# mitosis.net
KiCad netlist of a schematic drawn in Altium Designer
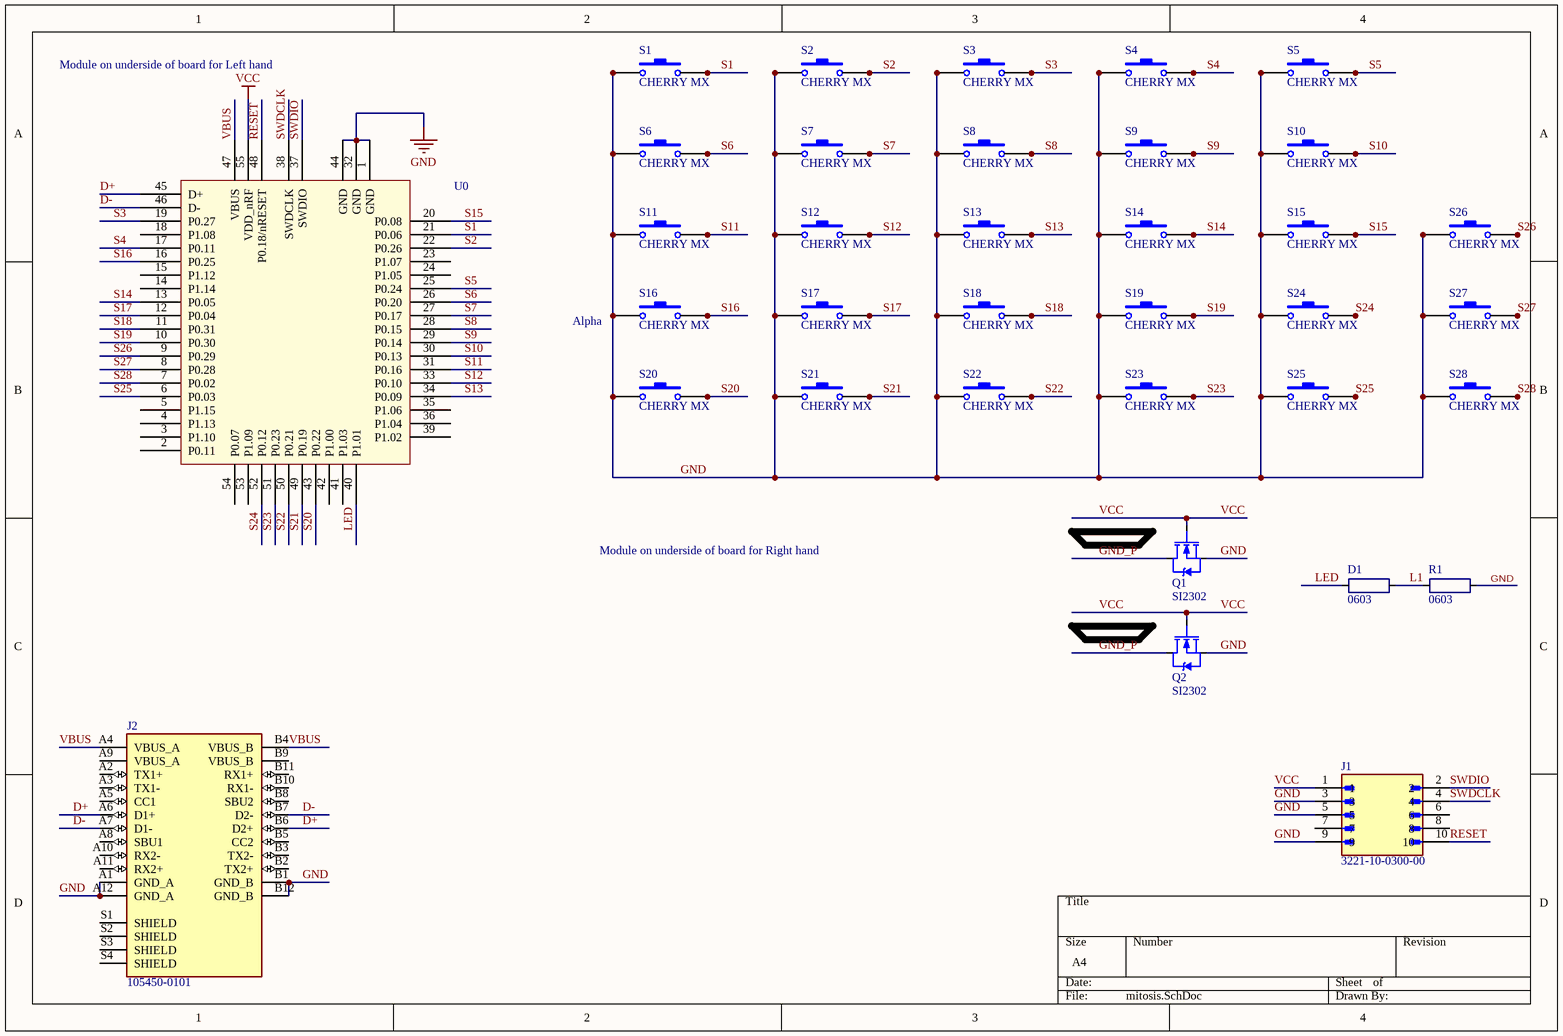
[diagram p0: mitosis.SchDoc]

(export (version "E")
  (design (tool "Eeschema 10.0.6"))
  (components
    (comp (ref "D1") (value "0603") (footprint "RESC2012X06N") (libsource (lib "SK") (part "0603")))
    (comp (ref "J1")
      (value "3221-10-0300-00")
      (footprint "mitosis:CNC_3221-10-0300-00")
      (description "Conn Shrouded Header HDR 10 POS 1.27mm Solder ST SMD T/R")
      (fields (field (name "MF") "CNC Tech") (field (name "MANUFACTURER PART NUMBER") "3221-10-0300-00-TR"))
      (libsource (lib "mitosis") (part "3221-10-0300-00"))
    )
    (comp (ref "J2")
      (value "105450-0101")
      (footprint "mitosis:MOLEX_105450-0101")
      (description "Conn USB 3.1 Type C F 24 POS Solder RA SMD 24 Terminal 1 Port USB 3.1 T/R")
      (fields (field (name "MANUFACTURER") "Molex"))
      (libsource (lib "mitosis") (part "105450-0101"))
    )
    (comp (ref "Q1")
      (value "SI2302")
      (footprint "SOT-23")
      (description "N-Channel Logic MOSFET")
      (fields (field (name "PUBLISHER") "Altium Limited"))
      (libsource (lib "SK") (part "SI2302"))
    )
    (comp (ref "Q2")
      (value "SI2302")
      (footprint "SOT-23")
      (description "N-Channel Logic MOSFET")
      (fields (field (name "PUBLISHER") "Altium Limited"))
      (libsource (lib "SK") (part "SI2302"))
    )
    (comp (ref "R1") (value "0603") (footprint "RESC2012X06N") (libsource (lib "SK") (part "0603")))
    (comp (ref "S1")
      (value "CHERRY MX")
      (footprint "cherry")
      (description "Switch")
      (fields (field (name "PUBLISHER") "Altium Limited"))
      (libsource (lib "SK") (part "CHERRY MX"))
    )
    (comp (ref "S2")
      (value "CHERRY MX")
      (footprint "cherry")
      (description "Switch")
      (fields (field (name "PUBLISHER") "Altium Limited"))
      (libsource (lib "SK") (part "CHERRY MX"))
    )
    (comp (ref "S3")
      (value "CHERRY MX")
      (footprint "cherry")
      (description "Switch")
      (fields (field (name "PUBLISHER") "Altium Limited"))
      (libsource (lib "SK") (part "CHERRY MX"))
    )
    (comp (ref "S4")
      (value "CHERRY MX")
      (footprint "cherry")
      (description "Switch")
      (fields (field (name "PUBLISHER") "Altium Limited"))
      (libsource (lib "SK") (part "CHERRY MX"))
    )
    (comp (ref "S5")
      (value "CHERRY MX")
      (footprint "cherry")
      (description "Switch")
      (fields (field (name "PUBLISHER") "Altium Limited"))
      (libsource (lib "SK") (part "CHERRY MX"))
    )
    (comp (ref "S6")
      (value "CHERRY MX")
      (footprint "cherry")
      (description "Switch")
      (fields (field (name "PUBLISHER") "Altium Limited"))
      (libsource (lib "SK") (part "CHERRY MX"))
    )
    (comp (ref "S7")
      (value "CHERRY MX")
      (footprint "cherry")
      (description "Switch")
      (fields (field (name "PUBLISHER") "Altium Limited"))
      (libsource (lib "SK") (part "CHERRY MX"))
    )
    (comp (ref "S8")
      (value "CHERRY MX")
      (footprint "cherry")
      (description "Switch")
      (fields (field (name "PUBLISHER") "Altium Limited"))
      (libsource (lib "SK") (part "CHERRY MX"))
    )
    (comp (ref "S9")
      (value "CHERRY MX")
      (footprint "cherry")
      (description "Switch")
      (fields (field (name "PUBLISHER") "Altium Limited"))
      (libsource (lib "SK") (part "CHERRY MX"))
    )
    (comp (ref "S10")
      (value "CHERRY MX")
      (footprint "cherry")
      (description "Switch")
      (fields (field (name "PUBLISHER") "Altium Limited"))
      (libsource (lib "SK") (part "CHERRY MX"))
    )
    (comp (ref "S11")
      (value "CHERRY MX")
      (footprint "cherry")
      (description "Switch")
      (fields (field (name "PUBLISHER") "Altium Limited"))
      (libsource (lib "SK") (part "CHERRY MX"))
    )
    (comp (ref "S12")
      (value "CHERRY MX")
      (footprint "cherry")
      (description "Switch")
      (fields (field (name "PUBLISHER") "Altium Limited"))
      (libsource (lib "SK") (part "CHERRY MX"))
    )
    (comp (ref "S13")
      (value "CHERRY MX")
      (footprint "cherry")
      (description "Switch")
      (fields (field (name "PUBLISHER") "Altium Limited"))
      (libsource (lib "SK") (part "CHERRY MX"))
    )
    (comp (ref "S14")
      (value "CHERRY MX")
      (footprint "cherry")
      (description "Switch")
      (fields (field (name "PUBLISHER") "Altium Limited"))
      (libsource (lib "SK") (part "CHERRY MX"))
    )
    (comp (ref "S15")
      (value "CHERRY MX")
      (footprint "cherry")
      (description "Switch")
      (fields (field (name "PUBLISHER") "Altium Limited"))
      (libsource (lib "SK") (part "CHERRY MX"))
    )
    (comp (ref "S16")
      (value "CHERRY MX")
      (footprint "cherry")
      (description "Switch")
      (fields (field (name "PUBLISHER") "Altium Limited"))
      (libsource (lib "SK") (part "CHERRY MX"))
    )
    (comp (ref "S17")
      (value "CHERRY MX")
      (footprint "cherry")
      (description "Switch")
      (fields (field (name "PUBLISHER") "Altium Limited"))
      (libsource (lib "SK") (part "CHERRY MX"))
    )
    (comp (ref "S18")
      (value "CHERRY MX")
      (footprint "cherry")
      (description "Switch")
      (fields (field (name "PUBLISHER") "Altium Limited"))
      (libsource (lib "SK") (part "CHERRY MX"))
    )
    (comp (ref "S19")
      (value "CHERRY MX")
      (footprint "cherry")
      (description "Switch")
      (fields (field (name "PUBLISHER") "Altium Limited"))
      (libsource (lib "SK") (part "CHERRY MX"))
    )
    (comp (ref "S20")
      (value "CHERRY MX")
      (footprint "cherry")
      (description "Switch")
      (fields (field (name "PUBLISHER") "Altium Limited"))
      (libsource (lib "SK") (part "CHERRY MX"))
    )
    (comp (ref "S21")
      (value "CHERRY MX")
      (footprint "cherry")
      (description "Switch")
      (fields (field (name "PUBLISHER") "Altium Limited"))
      (libsource (lib "SK") (part "CHERRY MX"))
    )
    (comp (ref "S22")
      (value "CHERRY MX")
      (footprint "cherry")
      (description "Switch")
      (fields (field (name "PUBLISHER") "Altium Limited"))
      (libsource (lib "SK") (part "CHERRY MX"))
    )
    (comp (ref "S23")
      (value "CHERRY MX")
      (footprint "cherry")
      (description "Switch")
      (fields (field (name "PUBLISHER") "Altium Limited"))
      (libsource (lib "SK") (part "CHERRY MX"))
    )
    (comp (ref "S24")
      (value "CHERRY MX")
      (footprint "cherry")
      (description "Switch")
      (fields (field (name "PUBLISHER") "Altium Limited"))
      (libsource (lib "mitosis") (part "CHERRY MX"))
    )
    (comp (ref "S25")
      (value "CHERRY MX")
      (footprint "cherry")
      (description "Switch")
      (fields (field (name "PUBLISHER") "Altium Limited"))
      (libsource (lib "mitosis") (part "CHERRY MX"))
    )
    (comp (ref "S26")
      (value "CHERRY MX")
      (footprint "cherry")
      (description "Switch")
      (fields (field (name "PUBLISHER") "Altium Limited"))
      (libsource (lib "mitosis") (part "CHERRY MX"))
    )
    (comp (ref "S27")
      (value "CHERRY MX")
      (footprint "cherry")
      (description "Switch")
      (fields (field (name "PUBLISHER") "Altium Limited"))
      (libsource (lib "mitosis") (part "CHERRY MX"))
    )
    (comp (ref "S28")
      (value "CHERRY MX")
      (footprint "cherry")
      (description "Switch")
      (fields (field (name "PUBLISHER") "Altium Limited"))
      (libsource (lib "mitosis") (part "CHERRY MX"))
    )
    (comp (ref "U0")
      (value "Core52840 (B)")
      (footprint "Core52840")
      (description "NRF52840 (B)")
      (libsource (lib "mitosis") (part "Core52840 (B)"))
    )
  )
  (nets
    (net (code "1") (name "/D+") (class "Default")
      (node (ref "J2") (pin "A6") (pinfunction "D1+_A6") (pintype "bidirectional"))
      (node (ref "J2") (pin "B6") (pinfunction "D2+_B6") (pintype "bidirectional"))
      (node (ref "U0") (pin "45") (pinfunction "D+_45") (pintype "passive"))
    )
    (net (code "2") (name "/D-") (class "Default")
      (node (ref "J2") (pin "A7") (pinfunction "D1-_A7") (pintype "bidirectional"))
      (node (ref "J2") (pin "B7") (pinfunction "D2-_B7") (pintype "bidirectional"))
      (node (ref "U0") (pin "46") (pinfunction "D-_46") (pintype "passive"))
    )
    (net (code "3") (name "/GND_P") (class "Default")
      (node (ref "Q1") (pin "3") (pinfunction "D_3") (pintype "passive"))
      (node (ref "Q2") (pin "3") (pinfunction "D_3") (pintype "passive"))
    )
    (net (code "4") (name "/L1") (class "Default")
      (node (ref "D1") (pin "1") (pinfunction "1_1") (pintype "passive"))
      (node (ref "R1") (pin "2") (pinfunction "2_2") (pintype "passive"))
    )
    (net (code "5") (name "/LED") (class "Default")
      (node (ref "D1") (pin "2") (pinfunction "2_2") (pintype "passive"))
      (node (ref "U0") (pin "40") (pinfunction "P1.01_40") (pintype "passive"))
    )
    (net (code "6") (name "/RESET") (class "Default")
      (node (ref "J1") (pin "10") (pinfunction "10_10") (pintype "passive"))
      (node (ref "U0") (pin "48") (pinfunction "P0.18/nRESET_48") (pintype "passive"))
    )
    (net (code "7") (name "/S1") (class "Default")
      (node (ref "S1") (pin "10") (pinfunction "10_10") (pintype "passive"))
      (node (ref "S1") (pin "12") (pinfunction "12_12") (pintype "passive"))
      (node (ref "S1") (pin "2") (pinfunction "2_2") (pintype "passive"))
      (node (ref "S1") (pin "4") (pinfunction "4_4") (pintype "passive"))
      (node (ref "S1") (pin "6") (pinfunction "6_6") (pintype "passive"))
      (node (ref "S1") (pin "8") (pinfunction "8_8") (pintype "passive"))
      (node (ref "U0") (pin "21") (pinfunction "P0.06_21") (pintype "passive"))
    )
    (net (code "8") (name "/S2") (class "Default")
      (node (ref "S2") (pin "10") (pinfunction "10_10") (pintype "passive"))
      (node (ref "S2") (pin "12") (pinfunction "12_12") (pintype "passive"))
      (node (ref "S2") (pin "2") (pinfunction "2_2") (pintype "passive"))
      (node (ref "S2") (pin "4") (pinfunction "4_4") (pintype "passive"))
      (node (ref "S2") (pin "6") (pinfunction "6_6") (pintype "passive"))
      (node (ref "S2") (pin "8") (pinfunction "8_8") (pintype "passive"))
      (node (ref "U0") (pin "22") (pinfunction "P0.26_22") (pintype "passive"))
    )
    (net (code "9") (name "/S3") (class "Default")
      (node (ref "S3") (pin "10") (pinfunction "10_10") (pintype "passive"))
      (node (ref "S3") (pin "12") (pinfunction "12_12") (pintype "passive"))
      (node (ref "S3") (pin "2") (pinfunction "2_2") (pintype "passive"))
      (node (ref "S3") (pin "4") (pinfunction "4_4") (pintype "passive"))
      (node (ref "S3") (pin "6") (pinfunction "6_6") (pintype "passive"))
      (node (ref "S3") (pin "8") (pinfunction "8_8") (pintype "passive"))
      (node (ref "U0") (pin "19") (pinfunction "P0.27_19") (pintype "passive"))
    )
    (net (code "10") (name "/S4") (class "Default")
      (node (ref "S4") (pin "10") (pinfunction "10_10") (pintype "passive"))
      (node (ref "S4") (pin "12") (pinfunction "12_12") (pintype "passive"))
      (node (ref "S4") (pin "2") (pinfunction "2_2") (pintype "passive"))
      (node (ref "S4") (pin "4") (pinfunction "4_4") (pintype "passive"))
      (node (ref "S4") (pin "6") (pinfunction "6_6") (pintype "passive"))
      (node (ref "S4") (pin "8") (pinfunction "8_8") (pintype "passive"))
      (node (ref "U0") (pin "17") (pinfunction "P0.11_17") (pintype "passive"))
    )
    (net (code "11") (name "/S5") (class "Default")
      (node (ref "S5") (pin "10") (pinfunction "10_10") (pintype "passive"))
      (node (ref "S5") (pin "12") (pinfunction "12_12") (pintype "passive"))
      (node (ref "S5") (pin "2") (pinfunction "2_2") (pintype "passive"))
      (node (ref "S5") (pin "4") (pinfunction "4_4") (pintype "passive"))
      (node (ref "S5") (pin "6") (pinfunction "6_6") (pintype "passive"))
      (node (ref "S5") (pin "8") (pinfunction "8_8") (pintype "passive"))
      (node (ref "U0") (pin "25") (pinfunction "P0.24_25") (pintype "passive"))
    )
    (net (code "12") (name "/S6") (class "Default")
      (node (ref "S6") (pin "10") (pinfunction "10_10") (pintype "passive"))
      (node (ref "S6") (pin "12") (pinfunction "12_12") (pintype "passive"))
      (node (ref "S6") (pin "2") (pinfunction "2_2") (pintype "passive"))
      (node (ref "S6") (pin "4") (pinfunction "4_4") (pintype "passive"))
      (node (ref "S6") (pin "6") (pinfunction "6_6") (pintype "passive"))
      (node (ref "S6") (pin "8") (pinfunction "8_8") (pintype "passive"))
      (node (ref "U0") (pin "26") (pinfunction "P0.20_26") (pintype "passive"))
    )
    (net (code "13") (name "/S7") (class "Default")
      (node (ref "S7") (pin "10") (pinfunction "10_10") (pintype "passive"))
      (node (ref "S7") (pin "12") (pinfunction "12_12") (pintype "passive"))
      (node (ref "S7") (pin "2") (pinfunction "2_2") (pintype "passive"))
      (node (ref "S7") (pin "4") (pinfunction "4_4") (pintype "passive"))
      (node (ref "S7") (pin "6") (pinfunction "6_6") (pintype "passive"))
      (node (ref "S7") (pin "8") (pinfunction "8_8") (pintype "passive"))
      (node (ref "U0") (pin "27") (pinfunction "P0.17_27") (pintype "passive"))
    )
    (net (code "14") (name "/S8") (class "Default")
      (node (ref "S8") (pin "10") (pinfunction "10_10") (pintype "passive"))
      (node (ref "S8") (pin "12") (pinfunction "12_12") (pintype "passive"))
      (node (ref "S8") (pin "2") (pinfunction "2_2") (pintype "passive"))
      (node (ref "S8") (pin "4") (pinfunction "4_4") (pintype "passive"))
      (node (ref "S8") (pin "6") (pinfunction "6_6") (pintype "passive"))
      (node (ref "S8") (pin "8") (pinfunction "8_8") (pintype "passive"))
      (node (ref "U0") (pin "28") (pinfunction "P0.15_28") (pintype "passive"))
    )
    (net (code "15") (name "/S9") (class "Default")
      (node (ref "S9") (pin "10") (pinfunction "10_10") (pintype "passive"))
      (node (ref "S9") (pin "12") (pinfunction "12_12") (pintype "passive"))
      (node (ref "S9") (pin "2") (pinfunction "2_2") (pintype "passive"))
      (node (ref "S9") (pin "4") (pinfunction "4_4") (pintype "passive"))
      (node (ref "S9") (pin "6") (pinfunction "6_6") (pintype "passive"))
      (node (ref "S9") (pin "8") (pinfunction "8_8") (pintype "passive"))
      (node (ref "U0") (pin "29") (pinfunction "P0.14_29") (pintype "passive"))
    )
    (net (code "16") (name "/S10") (class "Default")
      (node (ref "S10") (pin "10") (pinfunction "10_10") (pintype "passive"))
      (node (ref "S10") (pin "12") (pinfunction "12_12") (pintype "passive"))
      (node (ref "S10") (pin "2") (pinfunction "2_2") (pintype "passive"))
      (node (ref "S10") (pin "4") (pinfunction "4_4") (pintype "passive"))
      (node (ref "S10") (pin "6") (pinfunction "6_6") (pintype "passive"))
      (node (ref "S10") (pin "8") (pinfunction "8_8") (pintype "passive"))
      (node (ref "U0") (pin "30") (pinfunction "P0.13_30") (pintype "passive"))
    )
    (net (code "17") (name "/S11") (class "Default")
      (node (ref "S11") (pin "10") (pinfunction "10_10") (pintype "passive"))
      (node (ref "S11") (pin "12") (pinfunction "12_12") (pintype "passive"))
      (node (ref "S11") (pin "2") (pinfunction "2_2") (pintype "passive"))
      (node (ref "S11") (pin "4") (pinfunction "4_4") (pintype "passive"))
      (node (ref "S11") (pin "6") (pinfunction "6_6") (pintype "passive"))
      (node (ref "S11") (pin "8") (pinfunction "8_8") (pintype "passive"))
      (node (ref "U0") (pin "31") (pinfunction "P0.16_31") (pintype "passive"))
    )
    (net (code "18") (name "/S12") (class "Default")
      (node (ref "S12") (pin "10") (pinfunction "10_10") (pintype "passive"))
      (node (ref "S12") (pin "12") (pinfunction "12_12") (pintype "passive"))
      (node (ref "S12") (pin "2") (pinfunction "2_2") (pintype "passive"))
      (node (ref "S12") (pin "4") (pinfunction "4_4") (pintype "passive"))
      (node (ref "S12") (pin "6") (pinfunction "6_6") (pintype "passive"))
      (node (ref "S12") (pin "8") (pinfunction "8_8") (pintype "passive"))
      (node (ref "U0") (pin "33") (pinfunction "P0.10_33") (pintype "passive"))
    )
    (net (code "19") (name "/S13") (class "Default")
      (node (ref "S13") (pin "10") (pinfunction "10_10") (pintype "passive"))
      (node (ref "S13") (pin "12") (pinfunction "12_12") (pintype "passive"))
      (node (ref "S13") (pin "2") (pinfunction "2_2") (pintype "passive"))
      (node (ref "S13") (pin "4") (pinfunction "4_4") (pintype "passive"))
      (node (ref "S13") (pin "6") (pinfunction "6_6") (pintype "passive"))
      (node (ref "S13") (pin "8") (pinfunction "8_8") (pintype "passive"))
      (node (ref "U0") (pin "34") (pinfunction "P0.09_34") (pintype "passive"))
    )
    (net (code "20") (name "/S14") (class "Default")
      (node (ref "S14") (pin "10") (pinfunction "10_10") (pintype "passive"))
      (node (ref "S14") (pin "12") (pinfunction "12_12") (pintype "passive"))
      (node (ref "S14") (pin "2") (pinfunction "2_2") (pintype "passive"))
      (node (ref "S14") (pin "4") (pinfunction "4_4") (pintype "passive"))
      (node (ref "S14") (pin "6") (pinfunction "6_6") (pintype "passive"))
      (node (ref "S14") (pin "8") (pinfunction "8_8") (pintype "passive"))
      (node (ref "U0") (pin "13") (pinfunction "P0.05_13") (pintype "passive"))
    )
    (net (code "21") (name "/S15") (class "Default")
      (node (ref "S15") (pin "10") (pinfunction "10_10") (pintype "passive"))
      (node (ref "S15") (pin "12") (pinfunction "12_12") (pintype "passive"))
      (node (ref "S15") (pin "2") (pinfunction "2_2") (pintype "passive"))
      (node (ref "S15") (pin "4") (pinfunction "4_4") (pintype "passive"))
      (node (ref "S15") (pin "6") (pinfunction "6_6") (pintype "passive"))
      (node (ref "S15") (pin "8") (pinfunction "8_8") (pintype "passive"))
      (node (ref "U0") (pin "20") (pinfunction "P0.08_20") (pintype "passive"))
    )
    (net (code "22") (name "/S16") (class "Default")
      (node (ref "S16") (pin "10") (pinfunction "10_10") (pintype "passive"))
      (node (ref "S16") (pin "12") (pinfunction "12_12") (pintype "passive"))
      (node (ref "S16") (pin "2") (pinfunction "2_2") (pintype "passive"))
      (node (ref "S16") (pin "4") (pinfunction "4_4") (pintype "passive"))
      (node (ref "S16") (pin "6") (pinfunction "6_6") (pintype "passive"))
      (node (ref "S16") (pin "8") (pinfunction "8_8") (pintype "passive"))
      (node (ref "U0") (pin "16") (pinfunction "P0.25_16") (pintype "passive"))
    )
    (net (code "23") (name "/S17") (class "Default")
      (node (ref "S17") (pin "10") (pinfunction "10_10") (pintype "passive"))
      (node (ref "S17") (pin "12") (pinfunction "12_12") (pintype "passive"))
      (node (ref "S17") (pin "2") (pinfunction "2_2") (pintype "passive"))
      (node (ref "S17") (pin "4") (pinfunction "4_4") (pintype "passive"))
      (node (ref "S17") (pin "6") (pinfunction "6_6") (pintype "passive"))
      (node (ref "S17") (pin "8") (pinfunction "8_8") (pintype "passive"))
      (node (ref "U0") (pin "12") (pinfunction "P0.04_12") (pintype "passive"))
    )
    (net (code "24") (name "/S18") (class "Default")
      (node (ref "S18") (pin "10") (pinfunction "10_10") (pintype "passive"))
      (node (ref "S18") (pin "12") (pinfunction "12_12") (pintype "passive"))
      (node (ref "S18") (pin "2") (pinfunction "2_2") (pintype "passive"))
      (node (ref "S18") (pin "4") (pinfunction "4_4") (pintype "passive"))
      (node (ref "S18") (pin "6") (pinfunction "6_6") (pintype "passive"))
      (node (ref "S18") (pin "8") (pinfunction "8_8") (pintype "passive"))
      (node (ref "U0") (pin "11") (pinfunction "P0.31_11") (pintype "passive"))
    )
    (net (code "25") (name "/S19") (class "Default")
      (node (ref "S19") (pin "10") (pinfunction "10_10") (pintype "passive"))
      (node (ref "S19") (pin "12") (pinfunction "12_12") (pintype "passive"))
      (node (ref "S19") (pin "2") (pinfunction "2_2") (pintype "passive"))
      (node (ref "S19") (pin "4") (pinfunction "4_4") (pintype "passive"))
      (node (ref "S19") (pin "6") (pinfunction "6_6") (pintype "passive"))
      (node (ref "S19") (pin "8") (pinfunction "8_8") (pintype "passive"))
      (node (ref "U0") (pin "10") (pinfunction "P0.30_10") (pintype "passive"))
    )
    (net (code "26") (name "/S20") (class "Default")
      (node (ref "S20") (pin "10") (pinfunction "10_10") (pintype "passive"))
      (node (ref "S20") (pin "12") (pinfunction "12_12") (pintype "passive"))
      (node (ref "S20") (pin "2") (pinfunction "2_2") (pintype "passive"))
      (node (ref "S20") (pin "4") (pinfunction "4_4") (pintype "passive"))
      (node (ref "S20") (pin "6") (pinfunction "6_6") (pintype "passive"))
      (node (ref "S20") (pin "8") (pinfunction "8_8") (pintype "passive"))
      (node (ref "U0") (pin "43") (pinfunction "P0.22_43") (pintype "passive"))
    )
    (net (code "27") (name "/S21") (class "Default")
      (node (ref "S21") (pin "10") (pinfunction "10_10") (pintype "passive"))
      (node (ref "S21") (pin "12") (pinfunction "12_12") (pintype "passive"))
      (node (ref "S21") (pin "2") (pinfunction "2_2") (pintype "passive"))
      (node (ref "S21") (pin "4") (pinfunction "4_4") (pintype "passive"))
      (node (ref "S21") (pin "6") (pinfunction "6_6") (pintype "passive"))
      (node (ref "S21") (pin "8") (pinfunction "8_8") (pintype "passive"))
      (node (ref "U0") (pin "49") (pinfunction "P0.19_49") (pintype "passive"))
    )
    (net (code "28") (name "/S22") (class "Default")
      (node (ref "S22") (pin "10") (pinfunction "10_10") (pintype "passive"))
      (node (ref "S22") (pin "12") (pinfunction "12_12") (pintype "passive"))
      (node (ref "S22") (pin "2") (pinfunction "2_2") (pintype "passive"))
      (node (ref "S22") (pin "4") (pinfunction "4_4") (pintype "passive"))
      (node (ref "S22") (pin "6") (pinfunction "6_6") (pintype "passive"))
      (node (ref "S22") (pin "8") (pinfunction "8_8") (pintype "passive"))
      (node (ref "U0") (pin "50") (pinfunction "P0.21_50") (pintype "passive"))
    )
    (net (code "29") (name "/S23") (class "Default")
      (node (ref "S23") (pin "10") (pinfunction "10_10") (pintype "passive"))
      (node (ref "S23") (pin "12") (pinfunction "12_12") (pintype "passive"))
      (node (ref "S23") (pin "2") (pinfunction "2_2") (pintype "passive"))
      (node (ref "S23") (pin "4") (pinfunction "4_4") (pintype "passive"))
      (node (ref "S23") (pin "6") (pinfunction "6_6") (pintype "passive"))
      (node (ref "S23") (pin "8") (pinfunction "8_8") (pintype "passive"))
      (node (ref "U0") (pin "51") (pinfunction "P0.23_51") (pintype "passive"))
    )
    (net (code "30") (name "/S24") (class "Default")
      (node (ref "S24") (pin "10") (pinfunction "10_10") (pintype "passive"))
      (node (ref "S24") (pin "12") (pinfunction "12_12") (pintype "passive"))
      (node (ref "S24") (pin "2") (pinfunction "2_2") (pintype "passive"))
      (node (ref "S24") (pin "4") (pinfunction "4_4") (pintype "passive"))
      (node (ref "S24") (pin "6") (pinfunction "6_6") (pintype "passive"))
      (node (ref "S24") (pin "8") (pinfunction "8_8") (pintype "passive"))
      (node (ref "U0") (pin "52") (pinfunction "P0.12_52") (pintype "passive"))
    )
    (net (code "31") (name "/S25") (class "Default")
      (node (ref "S25") (pin "10") (pinfunction "10_10") (pintype "passive"))
      (node (ref "S25") (pin "12") (pinfunction "12_12") (pintype "passive"))
      (node (ref "S25") (pin "2") (pinfunction "2_2") (pintype "passive"))
      (node (ref "S25") (pin "4") (pinfunction "4_4") (pintype "passive"))
      (node (ref "S25") (pin "6") (pinfunction "6_6") (pintype "passive"))
      (node (ref "S25") (pin "8") (pinfunction "8_8") (pintype "passive"))
      (node (ref "U0") (pin "6") (pinfunction "P0.03_6") (pintype "passive"))
    )
    (net (code "32") (name "/S26") (class "Default")
      (node (ref "S26") (pin "10") (pinfunction "10_10") (pintype "passive"))
      (node (ref "S26") (pin "12") (pinfunction "12_12") (pintype "passive"))
      (node (ref "S26") (pin "2") (pinfunction "2_2") (pintype "passive"))
      (node (ref "S26") (pin "4") (pinfunction "4_4") (pintype "passive"))
      (node (ref "S26") (pin "6") (pinfunction "6_6") (pintype "passive"))
      (node (ref "S26") (pin "8") (pinfunction "8_8") (pintype "passive"))
      (node (ref "U0") (pin "9") (pinfunction "P0.29_9") (pintype "passive"))
    )
    (net (code "33") (name "/S27") (class "Default")
      (node (ref "S27") (pin "10") (pinfunction "10_10") (pintype "passive"))
      (node (ref "S27") (pin "12") (pinfunction "12_12") (pintype "passive"))
      (node (ref "S27") (pin "2") (pinfunction "2_2") (pintype "passive"))
      (node (ref "S27") (pin "4") (pinfunction "4_4") (pintype "passive"))
      (node (ref "S27") (pin "6") (pinfunction "6_6") (pintype "passive"))
      (node (ref "S27") (pin "8") (pinfunction "8_8") (pintype "passive"))
      (node (ref "U0") (pin "8") (pinfunction "P0.28_8") (pintype "passive"))
    )
    (net (code "34") (name "/S28") (class "Default")
      (node (ref "S28") (pin "10") (pinfunction "10_10") (pintype "passive"))
      (node (ref "S28") (pin "12") (pinfunction "12_12") (pintype "passive"))
      (node (ref "S28") (pin "2") (pinfunction "2_2") (pintype "passive"))
      (node (ref "S28") (pin "4") (pinfunction "4_4") (pintype "passive"))
      (node (ref "S28") (pin "6") (pinfunction "6_6") (pintype "passive"))
      (node (ref "S28") (pin "8") (pinfunction "8_8") (pintype "passive"))
      (node (ref "U0") (pin "7") (pinfunction "P0.02_7") (pintype "passive"))
    )
    (net (code "35") (name "/SWDCLK") (class "Default")
      (node (ref "J1") (pin "4") (pinfunction "4_4") (pintype "passive"))
      (node (ref "U0") (pin "38") (pinfunction "SWDCLK_38") (pintype "passive"))
    )
    (net (code "36") (name "/SWDIO") (class "Default")
      (node (ref "J1") (pin "2") (pinfunction "2_2") (pintype "passive"))
      (node (ref "U0") (pin "37") (pinfunction "SWDIO_37") (pintype "passive"))
    )
    (net (code "37") (name "/VBUS") (class "Default")
      (node (ref "J2") (pin "A4") (pinfunction "VBUS_A_A4") (pintype "power_in"))
      (node (ref "J2") (pin "B4") (pinfunction "VBUS_B_B4") (pintype "power_in"))
      (node (ref "U0") (pin "47") (pinfunction "VBUS_47") (pintype "passive"))
    )
    (net (code "38") (name "GND") (class "Default")
      (node (ref "J1") (pin "3") (pinfunction "3_3") (pintype "passive"))
      (node (ref "J1") (pin "5") (pinfunction "5_5") (pintype "passive"))
      (node (ref "J1") (pin "9") (pinfunction "9_9") (pintype "passive"))
      (node (ref "J2") (pin "A1") (pinfunction "GND_A_A1") (pintype "power_in"))
      (node (ref "J2") (pin "A12") (pinfunction "GND_A_A12") (pintype "power_in"))
      (node (ref "J2") (pin "B1") (pinfunction "GND_B_B1") (pintype "power_in"))
      (node (ref "J2") (pin "B12") (pinfunction "GND_B_B12") (pintype "power_in"))
      (node (ref "Q1") (pin "2") (pinfunction "S_2") (pintype "passive"))
      (node (ref "Q2") (pin "2") (pinfunction "S_2") (pintype "passive"))
      (node (ref "R1") (pin "1") (pinfunction "1_1") (pintype "passive"))
      (node (ref "S1") (pin "1") (pinfunction "1_1") (pintype "passive"))
      (node (ref "S1") (pin "11") (pinfunction "11_11") (pintype "passive"))
      (node (ref "S1") (pin "3") (pinfunction "3_3") (pintype "passive"))
      (node (ref "S1") (pin "5") (pinfunction "5_5") (pintype "passive"))
      (node (ref "S1") (pin "7") (pinfunction "7_7") (pintype "passive"))
      (node (ref "S1") (pin "9") (pinfunction "9_9") (pintype "passive"))
      (node (ref "S10") (pin "1") (pinfunction "1_1") (pintype "passive"))
      (node (ref "S10") (pin "11") (pinfunction "11_11") (pintype "passive"))
      (node (ref "S10") (pin "3") (pinfunction "3_3") (pintype "passive"))
      (node (ref "S10") (pin "5") (pinfunction "5_5") (pintype "passive"))
      (node (ref "S10") (pin "7") (pinfunction "7_7") (pintype "passive"))
      (node (ref "S10") (pin "9") (pinfunction "9_9") (pintype "passive"))
      (node (ref "S11") (pin "1") (pinfunction "1_1") (pintype "passive"))
      (node (ref "S11") (pin "11") (pinfunction "11_11") (pintype "passive"))
      (node (ref "S11") (pin "3") (pinfunction "3_3") (pintype "passive"))
      (node (ref "S11") (pin "5") (pinfunction "5_5") (pintype "passive"))
      (node (ref "S11") (pin "7") (pinfunction "7_7") (pintype "passive"))
      (node (ref "S11") (pin "9") (pinfunction "9_9") (pintype "passive"))
      (node (ref "S12") (pin "1") (pinfunction "1_1") (pintype "passive"))
      (node (ref "S12") (pin "11") (pinfunction "11_11") (pintype "passive"))
      (node (ref "S12") (pin "3") (pinfunction "3_3") (pintype "passive"))
      (node (ref "S12") (pin "5") (pinfunction "5_5") (pintype "passive"))
      (node (ref "S12") (pin "7") (pinfunction "7_7") (pintype "passive"))
      (node (ref "S12") (pin "9") (pinfunction "9_9") (pintype "passive"))
      (node (ref "S13") (pin "1") (pinfunction "1_1") (pintype "passive"))
      (node (ref "S13") (pin "11") (pinfunction "11_11") (pintype "passive"))
      (node (ref "S13") (pin "3") (pinfunction "3_3") (pintype "passive"))
      (node (ref "S13") (pin "5") (pinfunction "5_5") (pintype "passive"))
      (node (ref "S13") (pin "7") (pinfunction "7_7") (pintype "passive"))
      (node (ref "S13") (pin "9") (pinfunction "9_9") (pintype "passive"))
      (node (ref "S14") (pin "1") (pinfunction "1_1") (pintype "passive"))
      (node (ref "S14") (pin "11") (pinfunction "11_11") (pintype "passive"))
      (node (ref "S14") (pin "3") (pinfunction "3_3") (pintype "passive"))
      (node (ref "S14") (pin "5") (pinfunction "5_5") (pintype "passive"))
      (node (ref "S14") (pin "7") (pinfunction "7_7") (pintype "passive"))
      (node (ref "S14") (pin "9") (pinfunction "9_9") (pintype "passive"))
      (node (ref "S15") (pin "1") (pinfunction "1_1") (pintype "passive"))
      (node (ref "S15") (pin "11") (pinfunction "11_11") (pintype "passive"))
      (node (ref "S15") (pin "3") (pinfunction "3_3") (pintype "passive"))
      (node (ref "S15") (pin "5") (pinfunction "5_5") (pintype "passive"))
      (node (ref "S15") (pin "7") (pinfunction "7_7") (pintype "passive"))
      (node (ref "S15") (pin "9") (pinfunction "9_9") (pintype "passive"))
      (node (ref "S16") (pin "1") (pinfunction "1_1") (pintype "passive"))
      (node (ref "S16") (pin "11") (pinfunction "11_11") (pintype "passive"))
      (node (ref "S16") (pin "3") (pinfunction "3_3") (pintype "passive"))
      (node (ref "S16") (pin "5") (pinfunction "5_5") (pintype "passive"))
      (node (ref "S16") (pin "7") (pinfunction "7_7") (pintype "passive"))
      (node (ref "S16") (pin "9") (pinfunction "9_9") (pintype "passive"))
      (node (ref "S17") (pin "1") (pinfunction "1_1") (pintype "passive"))
      (node (ref "S17") (pin "11") (pinfunction "11_11") (pintype "passive"))
      (node (ref "S17") (pin "3") (pinfunction "3_3") (pintype "passive"))
      (node (ref "S17") (pin "5") (pinfunction "5_5") (pintype "passive"))
      (node (ref "S17") (pin "7") (pinfunction "7_7") (pintype "passive"))
      (node (ref "S17") (pin "9") (pinfunction "9_9") (pintype "passive"))
      (node (ref "S18") (pin "1") (pinfunction "1_1") (pintype "passive"))
      (node (ref "S18") (pin "11") (pinfunction "11_11") (pintype "passive"))
      (node (ref "S18") (pin "3") (pinfunction "3_3") (pintype "passive"))
      (node (ref "S18") (pin "5") (pinfunction "5_5") (pintype "passive"))
      (node (ref "S18") (pin "7") (pinfunction "7_7") (pintype "passive"))
      (node (ref "S18") (pin "9") (pinfunction "9_9") (pintype "passive"))
      (node (ref "S19") (pin "1") (pinfunction "1_1") (pintype "passive"))
      (node (ref "S19") (pin "11") (pinfunction "11_11") (pintype "passive"))
      (node (ref "S19") (pin "3") (pinfunction "3_3") (pintype "passive"))
      (node (ref "S19") (pin "5") (pinfunction "5_5") (pintype "passive"))
      (node (ref "S19") (pin "7") (pinfunction "7_7") (pintype "passive"))
      (node (ref "S19") (pin "9") (pinfunction "9_9") (pintype "passive"))
      (node (ref "S2") (pin "1") (pinfunction "1_1") (pintype "passive"))
      (node (ref "S2") (pin "11") (pinfunction "11_11") (pintype "passive"))
      (node (ref "S2") (pin "3") (pinfunction "3_3") (pintype "passive"))
      (node (ref "S2") (pin "5") (pinfunction "5_5") (pintype "passive"))
      (node (ref "S2") (pin "7") (pinfunction "7_7") (pintype "passive"))
      (node (ref "S2") (pin "9") (pinfunction "9_9") (pintype "passive"))
      (node (ref "S20") (pin "1") (pinfunction "1_1") (pintype "passive"))
      (node (ref "S20") (pin "11") (pinfunction "11_11") (pintype "passive"))
      (node (ref "S20") (pin "3") (pinfunction "3_3") (pintype "passive"))
      (node (ref "S20") (pin "5") (pinfunction "5_5") (pintype "passive"))
      (node (ref "S20") (pin "7") (pinfunction "7_7") (pintype "passive"))
      (node (ref "S20") (pin "9") (pinfunction "9_9") (pintype "passive"))
      (node (ref "S21") (pin "1") (pinfunction "1_1") (pintype "passive"))
      (node (ref "S21") (pin "11") (pinfunction "11_11") (pintype "passive"))
      (node (ref "S21") (pin "3") (pinfunction "3_3") (pintype "passive"))
      (node (ref "S21") (pin "5") (pinfunction "5_5") (pintype "passive"))
      (node (ref "S21") (pin "7") (pinfunction "7_7") (pintype "passive"))
      (node (ref "S21") (pin "9") (pinfunction "9_9") (pintype "passive"))
      (node (ref "S22") (pin "1") (pinfunction "1_1") (pintype "passive"))
      (node (ref "S22") (pin "11") (pinfunction "11_11") (pintype "passive"))
      (node (ref "S22") (pin "3") (pinfunction "3_3") (pintype "passive"))
      (node (ref "S22") (pin "5") (pinfunction "5_5") (pintype "passive"))
      (node (ref "S22") (pin "7") (pinfunction "7_7") (pintype "passive"))
      (node (ref "S22") (pin "9") (pinfunction "9_9") (pintype "passive"))
      (node (ref "S23") (pin "1") (pinfunction "1_1") (pintype "passive"))
      (node (ref "S23") (pin "11") (pinfunction "11_11") (pintype "passive"))
      (node (ref "S23") (pin "3") (pinfunction "3_3") (pintype "passive"))
      (node (ref "S23") (pin "5") (pinfunction "5_5") (pintype "passive"))
      (node (ref "S23") (pin "7") (pinfunction "7_7") (pintype "passive"))
      (node (ref "S23") (pin "9") (pinfunction "9_9") (pintype "passive"))
      (node (ref "S24") (pin "1") (pinfunction "1_1") (pintype "passive"))
      (node (ref "S24") (pin "11") (pinfunction "11_11") (pintype "passive"))
      (node (ref "S24") (pin "3") (pinfunction "3_3") (pintype "passive"))
      (node (ref "S24") (pin "5") (pinfunction "5_5") (pintype "passive"))
      (node (ref "S24") (pin "7") (pinfunction "7_7") (pintype "passive"))
      (node (ref "S24") (pin "9") (pinfunction "9_9") (pintype "passive"))
      (node (ref "S25") (pin "1") (pinfunction "1_1") (pintype "passive"))
      (node (ref "S25") (pin "11") (pinfunction "11_11") (pintype "passive"))
      (node (ref "S25") (pin "3") (pinfunction "3_3") (pintype "passive"))
      (node (ref "S25") (pin "5") (pinfunction "5_5") (pintype "passive"))
      (node (ref "S25") (pin "7") (pinfunction "7_7") (pintype "passive"))
      (node (ref "S25") (pin "9") (pinfunction "9_9") (pintype "passive"))
      (node (ref "S26") (pin "1") (pinfunction "1_1") (pintype "passive"))
      (node (ref "S26") (pin "11") (pinfunction "11_11") (pintype "passive"))
      (node (ref "S26") (pin "3") (pinfunction "3_3") (pintype "passive"))
      (node (ref "S26") (pin "5") (pinfunction "5_5") (pintype "passive"))
      (node (ref "S26") (pin "7") (pinfunction "7_7") (pintype "passive"))
      (node (ref "S26") (pin "9") (pinfunction "9_9") (pintype "passive"))
      (node (ref "S27") (pin "1") (pinfunction "1_1") (pintype "passive"))
      (node (ref "S27") (pin "11") (pinfunction "11_11") (pintype "passive"))
      (node (ref "S27") (pin "3") (pinfunction "3_3") (pintype "passive"))
      (node (ref "S27") (pin "5") (pinfunction "5_5") (pintype "passive"))
      (node (ref "S27") (pin "7") (pinfunction "7_7") (pintype "passive"))
      (node (ref "S27") (pin "9") (pinfunction "9_9") (pintype "passive"))
      (node (ref "S28") (pin "1") (pinfunction "1_1") (pintype "passive"))
      (node (ref "S28") (pin "11") (pinfunction "11_11") (pintype "passive"))
      (node (ref "S28") (pin "3") (pinfunction "3_3") (pintype "passive"))
      (node (ref "S28") (pin "5") (pinfunction "5_5") (pintype "passive"))
      (node (ref "S28") (pin "7") (pinfunction "7_7") (pintype "passive"))
      (node (ref "S28") (pin "9") (pinfunction "9_9") (pintype "passive"))
      (node (ref "S3") (pin "1") (pinfunction "1_1") (pintype "passive"))
      (node (ref "S3") (pin "11") (pinfunction "11_11") (pintype "passive"))
      (node (ref "S3") (pin "3") (pinfunction "3_3") (pintype "passive"))
      (node (ref "S3") (pin "5") (pinfunction "5_5") (pintype "passive"))
      (node (ref "S3") (pin "7") (pinfunction "7_7") (pintype "passive"))
      (node (ref "S3") (pin "9") (pinfunction "9_9") (pintype "passive"))
      (node (ref "S4") (pin "1") (pinfunction "1_1") (pintype "passive"))
      (node (ref "S4") (pin "11") (pinfunction "11_11") (pintype "passive"))
      (node (ref "S4") (pin "3") (pinfunction "3_3") (pintype "passive"))
      (node (ref "S4") (pin "5") (pinfunction "5_5") (pintype "passive"))
      (node (ref "S4") (pin "7") (pinfunction "7_7") (pintype "passive"))
      (node (ref "S4") (pin "9") (pinfunction "9_9") (pintype "passive"))
      (node (ref "S5") (pin "1") (pinfunction "1_1") (pintype "passive"))
      (node (ref "S5") (pin "11") (pinfunction "11_11") (pintype "passive"))
      (node (ref "S5") (pin "3") (pinfunction "3_3") (pintype "passive"))
      (node (ref "S5") (pin "5") (pinfunction "5_5") (pintype "passive"))
      (node (ref "S5") (pin "7") (pinfunction "7_7") (pintype "passive"))
      (node (ref "S5") (pin "9") (pinfunction "9_9") (pintype "passive"))
      (node (ref "S6") (pin "1") (pinfunction "1_1") (pintype "passive"))
      (node (ref "S6") (pin "11") (pinfunction "11_11") (pintype "passive"))
      (node (ref "S6") (pin "3") (pinfunction "3_3") (pintype "passive"))
      (node (ref "S6") (pin "5") (pinfunction "5_5") (pintype "passive"))
      (node (ref "S6") (pin "7") (pinfunction "7_7") (pintype "passive"))
      (node (ref "S6") (pin "9") (pinfunction "9_9") (pintype "passive"))
      (node (ref "S7") (pin "1") (pinfunction "1_1") (pintype "passive"))
      (node (ref "S7") (pin "11") (pinfunction "11_11") (pintype "passive"))
      (node (ref "S7") (pin "3") (pinfunction "3_3") (pintype "passive"))
      (node (ref "S7") (pin "5") (pinfunction "5_5") (pintype "passive"))
      (node (ref "S7") (pin "7") (pinfunction "7_7") (pintype "passive"))
      (node (ref "S7") (pin "9") (pinfunction "9_9") (pintype "passive"))
      (node (ref "S8") (pin "1") (pinfunction "1_1") (pintype "passive"))
      (node (ref "S8") (pin "11") (pinfunction "11_11") (pintype "passive"))
      (node (ref "S8") (pin "3") (pinfunction "3_3") (pintype "passive"))
      (node (ref "S8") (pin "5") (pinfunction "5_5") (pintype "passive"))
      (node (ref "S8") (pin "7") (pinfunction "7_7") (pintype "passive"))
      (node (ref "S8") (pin "9") (pinfunction "9_9") (pintype "passive"))
      (node (ref "S9") (pin "1") (pinfunction "1_1") (pintype "passive"))
      (node (ref "S9") (pin "11") (pinfunction "11_11") (pintype "passive"))
      (node (ref "S9") (pin "3") (pinfunction "3_3") (pintype "passive"))
      (node (ref "S9") (pin "5") (pinfunction "5_5") (pintype "passive"))
      (node (ref "S9") (pin "7") (pinfunction "7_7") (pintype "passive"))
      (node (ref "S9") (pin "9") (pinfunction "9_9") (pintype "passive"))
      (node (ref "U0") (pin "1") (pinfunction "GND_1") (pintype "passive"))
      (node (ref "U0") (pin "32") (pinfunction "GND_32") (pintype "passive"))
      (node (ref "U0") (pin "44") (pinfunction "GND_44") (pintype "passive"))
    )
    (net (code "39") (name "VCC") (class "Default")
      (node (ref "J1") (pin "1") (pinfunction "1_1") (pintype "passive"))
      (node (ref "Q1") (pin "1") (pinfunction "G_1") (pintype "passive"))
      (node (ref "Q2") (pin "1") (pinfunction "G_1") (pintype "passive"))
      (node (ref "U0") (pin "55") (pinfunction "VDD_nRF_55") (pintype "passive"))
    )
    (net (code "40") (name "unconnected-(J1-Pad6)") (class "Default")
      (node (ref "J1") (pin "6") (pinfunction "6_6") (pintype "passive"))
    )
    (net (code "41") (name "unconnected-(J1-Pad7)") (class "Default")
      (node (ref "J1") (pin "7") (pinfunction "7_7") (pintype "passive"))
    )
    (net (code "42") (name "unconnected-(J1-Pad8)") (class "Default")
      (node (ref "J1") (pin "8") (pinfunction "8_8") (pintype "passive"))
    )
    (net (code "43") (name "unconnected-(J2-CC1-PadA5)") (class "Default")
      (node (ref "J2") (pin "A5") (pinfunction "CC1_A5") (pintype "bidirectional"))
    )
    (net (code "44") (name "unconnected-(J2-CC2-PadB5)") (class "Default")
      (node (ref "J2") (pin "B5") (pinfunction "CC2_B5") (pintype "bidirectional"))
    )
    (net (code "45") (name "unconnected-(J2-RX1+-PadB11)") (class "Default")
      (node (ref "J2") (pin "B11") (pinfunction "RX1+_B11") (pintype "bidirectional"))
    )
    (net (code "46") (name "unconnected-(J2-RX1--PadB10)") (class "Default")
      (node (ref "J2") (pin "B10") (pinfunction "RX1-_B10") (pintype "bidirectional"))
    )
    (net (code "47") (name "unconnected-(J2-RX2+-PadA11)") (class "Default")
      (node (ref "J2") (pin "A11") (pinfunction "RX2+_A11") (pintype "bidirectional"))
    )
    (net (code "48") (name "unconnected-(J2-RX2--PadA10)") (class "Default")
      (node (ref "J2") (pin "A10") (pinfunction "RX2-_A10") (pintype "bidirectional"))
    )
    (net (code "49") (name "unconnected-(J2-SBU1-PadA8)") (class "Default")
      (node (ref "J2") (pin "A8") (pinfunction "SBU1_A8") (pintype "bidirectional"))
    )
    (net (code "50") (name "unconnected-(J2-SBU2-PadB8)") (class "Default")
      (node (ref "J2") (pin "B8") (pinfunction "SBU2_B8") (pintype "bidirectional"))
    )
    (net (code "51") (name "unconnected-(J2-SHIELD-PadS1)") (class "Default")
      (node (ref "J2") (pin "S1") (pinfunction "SHIELD_S1") (pintype "passive"))
    )
    (net (code "52") (name "unconnected-(J2-SHIELD-PadS2)") (class "Default")
      (node (ref "J2") (pin "S2") (pinfunction "SHIELD_S2") (pintype "passive"))
    )
    (net (code "53") (name "unconnected-(J2-SHIELD-PadS3)") (class "Default")
      (node (ref "J2") (pin "S3") (pinfunction "SHIELD_S3") (pintype "passive"))
    )
    (net (code "54") (name "unconnected-(J2-SHIELD-PadS4)") (class "Default")
      (node (ref "J2") (pin "S4") (pinfunction "SHIELD_S4") (pintype "passive"))
    )
    (net (code "55") (name "unconnected-(J2-TX1+-PadA2)") (class "Default")
      (node (ref "J2") (pin "A2") (pinfunction "TX1+_A2") (pintype "bidirectional"))
    )
    (net (code "56") (name "unconnected-(J2-TX1--PadA3)") (class "Default")
      (node (ref "J2") (pin "A3") (pinfunction "TX1-_A3") (pintype "bidirectional"))
    )
    (net (code "57") (name "unconnected-(J2-TX2+-PadB2)") (class "Default")
      (node (ref "J2") (pin "B2") (pinfunction "TX2+_B2") (pintype "bidirectional"))
    )
    (net (code "58") (name "unconnected-(J2-TX2--PadB3)") (class "Default")
      (node (ref "J2") (pin "B3") (pinfunction "TX2-_B3") (pintype "bidirectional"))
    )
    (net (code "59") (name "unconnected-(J2-VBUS_A-PadA9)") (class "Default")
      (node (ref "J2") (pin "A9") (pinfunction "VBUS_A_A9") (pintype "power_in"))
    )
    (net (code "60") (name "unconnected-(J2-VBUS_B-PadB9)") (class "Default")
      (node (ref "J2") (pin "B9") (pinfunction "VBUS_B_B9") (pintype "power_in"))
    )
    (net (code "61") (name "unconnected-(U0-P0.07-Pad54)") (class "Default")
      (node (ref "U0") (pin "54") (pinfunction "P0.07_54") (pintype "passive"))
    )
    (net (code "62") (name "unconnected-(U0-P0.11-Pad2)") (class "Default")
      (node (ref "U0") (pin "2") (pinfunction "P0.11_2") (pintype "passive"))
    )
    (net (code "63") (name "unconnected-(U0-P1.00-Pad42)") (class "Default")
      (node (ref "U0") (pin "42") (pinfunction "P1.00_42") (pintype "passive"))
    )
    (net (code "64") (name "unconnected-(U0-P1.02-Pad39)") (class "Default")
      (node (ref "U0") (pin "39") (pinfunction "P1.02_39") (pintype "passive"))
    )
    (net (code "65") (name "unconnected-(U0-P1.03-Pad41)") (class "Default")
      (node (ref "U0") (pin "41") (pinfunction "P1.03_41") (pintype "passive"))
    )
    (net (code "66") (name "unconnected-(U0-P1.04-Pad36)") (class "Default")
      (node (ref "U0") (pin "36") (pinfunction "P1.04_36") (pintype "passive"))
    )
    (net (code "67") (name "unconnected-(U0-P1.05-Pad24)") (class "Default")
      (node (ref "U0") (pin "24") (pinfunction "P1.05_24") (pintype "passive"))
    )
    (net (code "68") (name "unconnected-(U0-P1.06-Pad35)") (class "Default")
      (node (ref "U0") (pin "35") (pinfunction "P1.06_35") (pintype "passive"))
    )
    (net (code "69") (name "unconnected-(U0-P1.07-Pad23)") (class "Default")
      (node (ref "U0") (pin "23") (pinfunction "P1.07_23") (pintype "passive"))
    )
    (net (code "70") (name "unconnected-(U0-P1.08-Pad18)") (class "Default")
      (node (ref "U0") (pin "18") (pinfunction "P1.08_18") (pintype "passive"))
    )
    (net (code "71") (name "unconnected-(U0-P1.09-Pad53)") (class "Default")
      (node (ref "U0") (pin "53") (pinfunction "P1.09_53") (pintype "passive"))
    )
    (net (code "72") (name "unconnected-(U0-P1.10-Pad3)") (class "Default")
      (node (ref "U0") (pin "3") (pinfunction "P1.10_3") (pintype "passive"))
    )
    (net (code "73") (name "unconnected-(U0-P1.12-Pad15)") (class "Default")
      (node (ref "U0") (pin "15") (pinfunction "P1.12_15") (pintype "passive"))
    )
    (net (code "74") (name "unconnected-(U0-P1.13-Pad4)") (class "Default")
      (node (ref "U0") (pin "4") (pinfunction "P1.13_4") (pintype "passive"))
    )
    (net (code "75") (name "unconnected-(U0-P1.14-Pad14)") (class "Default")
      (node (ref "U0") (pin "14") (pinfunction "P1.14_14") (pintype "passive"))
    )
    (net (code "76") (name "unconnected-(U0-P1.15-Pad5)") (class "Default")
      (node (ref "U0") (pin "5") (pinfunction "P1.15_5") (pintype "passive"))
    )
  )
)
